# Input_v2_0.net
KiCad netlist of a schematic drawn in EAGLE
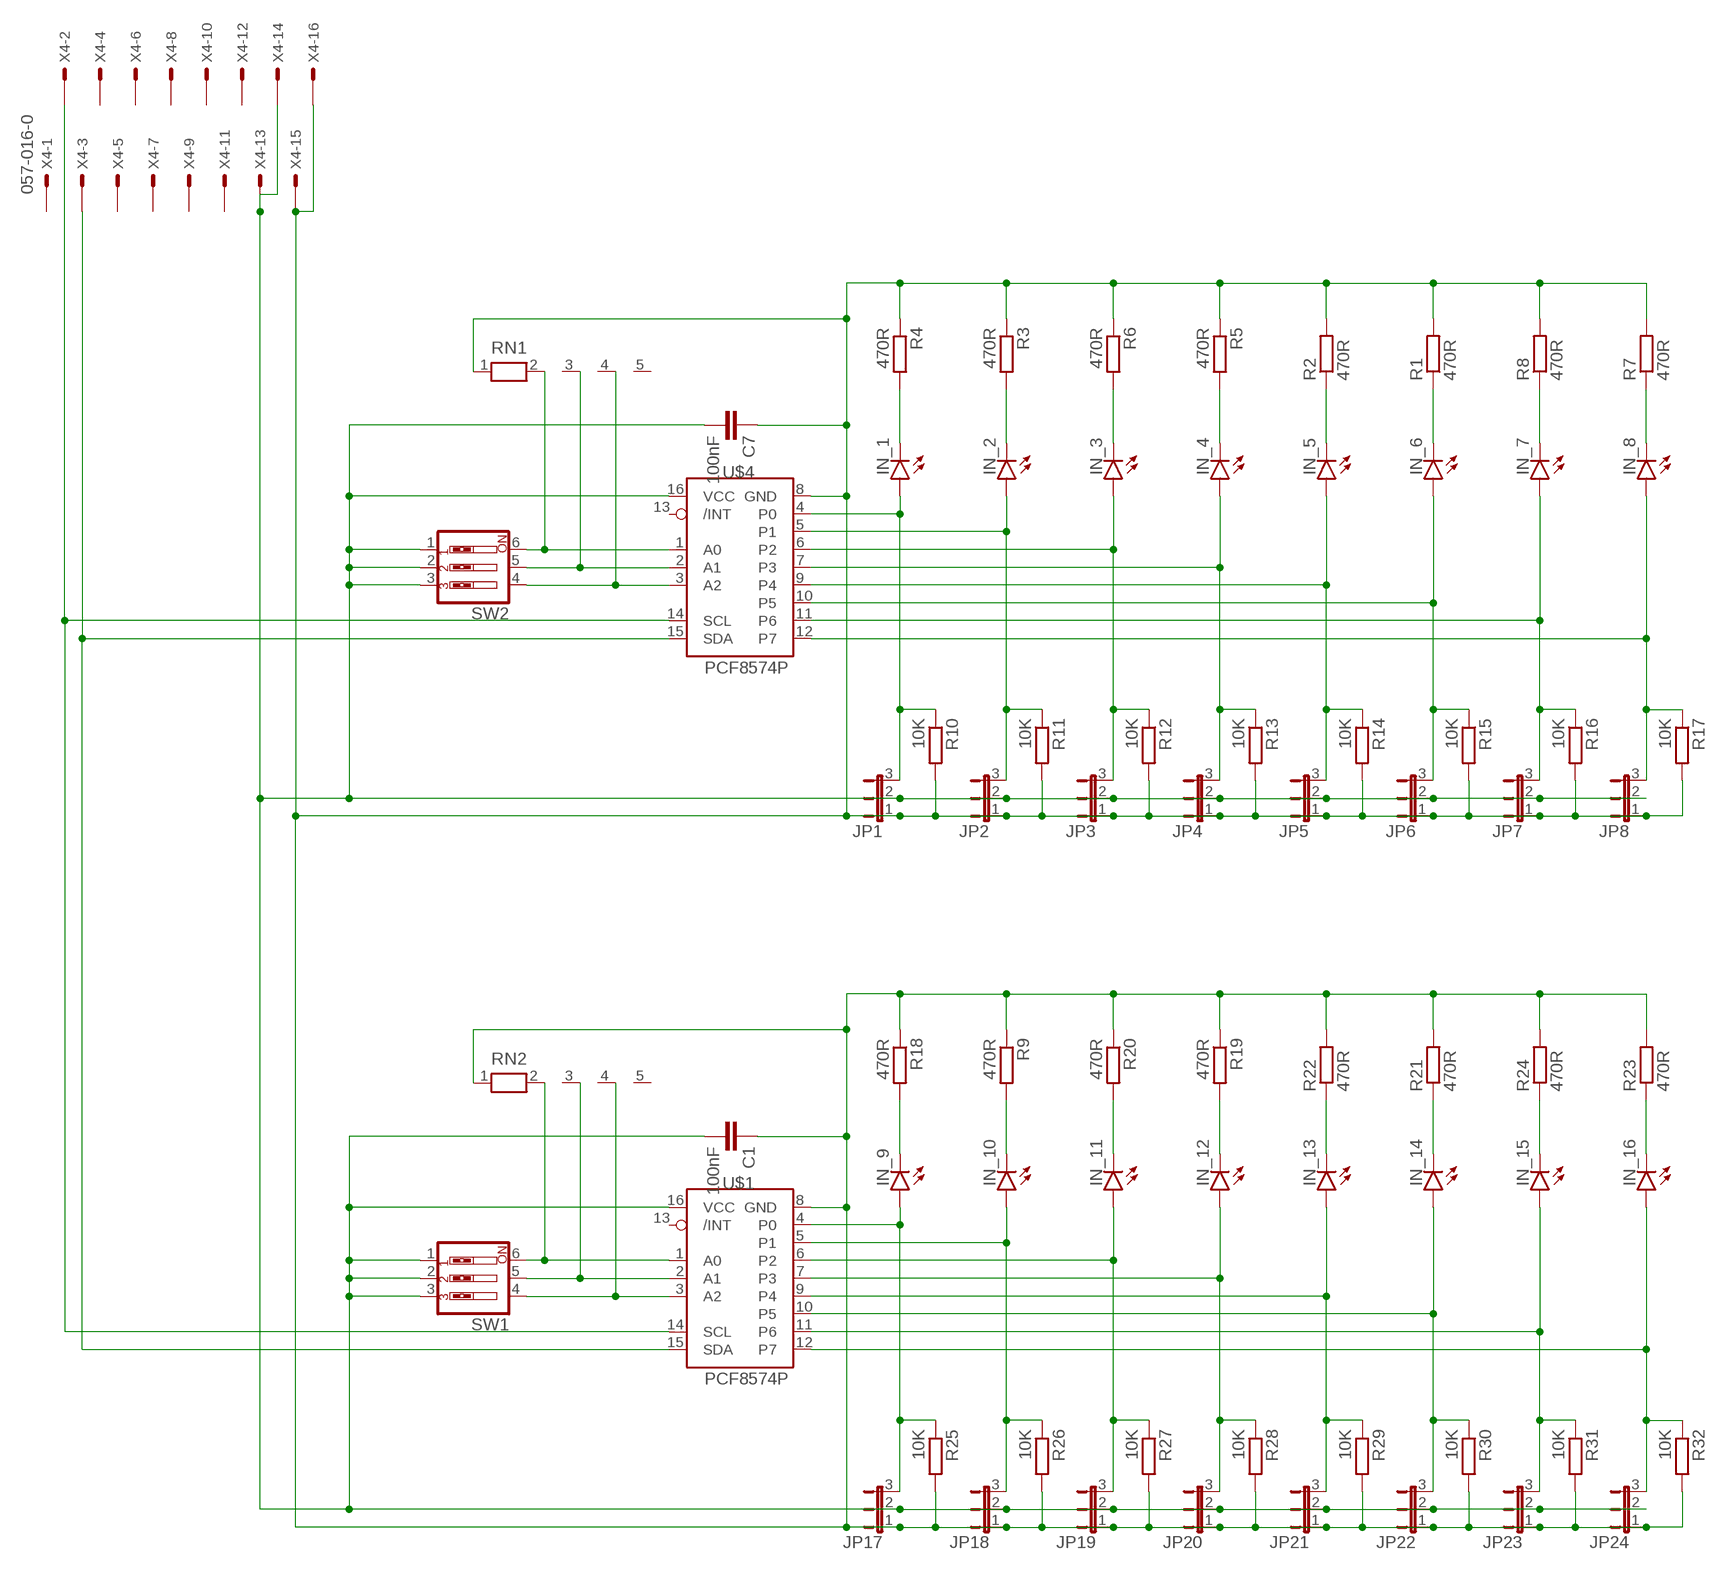
[diagram p0: schematic, sheet 1]

(export (version "E")
  (design (tool "Eeschema 10.0.6"))
  (components
    (comp (ref "C1")
      (value "100nF")
      (footprint "eagle-import:C025-024X044")
      (libsource (lib "eagle-import") (part "C-EU025-024X044"))
    )
    (comp (ref "C7")
      (value "100nF")
      (footprint "eagle-import:C025-024X044")
      (libsource (lib "eagle-import") (part "C-EU025-024X044"))
    )
    (comp (ref "IN_1")
      (value "LED3MM")
      (footprint "eagle-import:LED3MM")
      (libsource (lib "eagle-import") (part "LED3MM"))
    )
    (comp (ref "IN_2")
      (value "LED3MM")
      (footprint "eagle-import:LED3MM")
      (libsource (lib "eagle-import") (part "LED3MM"))
    )
    (comp (ref "IN_3")
      (value "LED3MM")
      (footprint "eagle-import:LED3MM")
      (libsource (lib "eagle-import") (part "LED3MM"))
    )
    (comp (ref "IN_4")
      (value "LED3MM")
      (footprint "eagle-import:LED3MM")
      (libsource (lib "eagle-import") (part "LED3MM"))
    )
    (comp (ref "IN_5")
      (value "LED3MM")
      (footprint "eagle-import:LED3MM")
      (libsource (lib "eagle-import") (part "LED3MM"))
    )
    (comp (ref "IN_6")
      (value "LED3MM")
      (footprint "eagle-import:LED3MM")
      (libsource (lib "eagle-import") (part "LED3MM"))
    )
    (comp (ref "IN_7")
      (value "LED3MM")
      (footprint "eagle-import:LED3MM")
      (libsource (lib "eagle-import") (part "LED3MM"))
    )
    (comp (ref "IN_8")
      (value "LED3MM")
      (footprint "eagle-import:LED3MM")
      (libsource (lib "eagle-import") (part "LED3MM"))
    )
    (comp (ref "IN_9")
      (value "LED3MM")
      (footprint "eagle-import:LED3MM")
      (libsource (lib "eagle-import") (part "LED3MM"))
    )
    (comp (ref "IN_10")
      (value "LED3MM")
      (footprint "eagle-import:LED3MM")
      (libsource (lib "eagle-import") (part "LED3MM"))
    )
    (comp (ref "IN_11")
      (value "LED3MM")
      (footprint "eagle-import:LED3MM")
      (libsource (lib "eagle-import") (part "LED3MM"))
    )
    (comp (ref "IN_12")
      (value "LED3MM")
      (footprint "eagle-import:LED3MM")
      (libsource (lib "eagle-import") (part "LED3MM"))
    )
    (comp (ref "IN_13")
      (value "LED3MM")
      (footprint "eagle-import:LED3MM")
      (libsource (lib "eagle-import") (part "LED3MM"))
    )
    (comp (ref "IN_14")
      (value "LED3MM")
      (footprint "eagle-import:LED3MM")
      (libsource (lib "eagle-import") (part "LED3MM"))
    )
    (comp (ref "IN_15")
      (value "LED3MM")
      (footprint "eagle-import:LED3MM")
      (libsource (lib "eagle-import") (part "LED3MM"))
    )
    (comp (ref "IN_16")
      (value "LED3MM")
      (footprint "eagle-import:LED3MM")
      (libsource (lib "eagle-import") (part "LED3MM"))
    )
    (comp (ref "JP1")
      (value "JP2E")
      (footprint "eagle-import:JP2")
      (libsource (lib "eagle-import") (part "JP2E"))
    )
    (comp (ref "JP2")
      (value "JP2E")
      (footprint "eagle-import:JP2")
      (libsource (lib "eagle-import") (part "JP2E"))
    )
    (comp (ref "JP3")
      (value "JP2E")
      (footprint "eagle-import:JP2")
      (libsource (lib "eagle-import") (part "JP2E"))
    )
    (comp (ref "JP4")
      (value "JP2E")
      (footprint "eagle-import:JP2")
      (libsource (lib "eagle-import") (part "JP2E"))
    )
    (comp (ref "JP5")
      (value "JP2E")
      (footprint "eagle-import:JP2")
      (libsource (lib "eagle-import") (part "JP2E"))
    )
    (comp (ref "JP6")
      (value "JP2E")
      (footprint "eagle-import:JP2")
      (libsource (lib "eagle-import") (part "JP2E"))
    )
    (comp (ref "JP7")
      (value "JP2E")
      (footprint "eagle-import:JP2")
      (libsource (lib "eagle-import") (part "JP2E"))
    )
    (comp (ref "JP8")
      (value "JP2E")
      (footprint "eagle-import:JP2")
      (libsource (lib "eagle-import") (part "JP2E"))
    )
    (comp (ref "JP17")
      (value "JP2E")
      (footprint "eagle-import:JP2")
      (libsource (lib "eagle-import") (part "JP2E"))
    )
    (comp (ref "JP18")
      (value "JP2E")
      (footprint "eagle-import:JP2")
      (libsource (lib "eagle-import") (part "JP2E"))
    )
    (comp (ref "JP19")
      (value "JP2E")
      (footprint "eagle-import:JP2")
      (libsource (lib "eagle-import") (part "JP2E"))
    )
    (comp (ref "JP20")
      (value "JP2E")
      (footprint "eagle-import:JP2")
      (libsource (lib "eagle-import") (part "JP2E"))
    )
    (comp (ref "JP21")
      (value "JP2E")
      (footprint "eagle-import:JP2")
      (libsource (lib "eagle-import") (part "JP2E"))
    )
    (comp (ref "JP22")
      (value "JP2E")
      (footprint "eagle-import:JP2")
      (libsource (lib "eagle-import") (part "JP2E"))
    )
    (comp (ref "JP23")
      (value "JP2E")
      (footprint "eagle-import:JP2")
      (libsource (lib "eagle-import") (part "JP2E"))
    )
    (comp (ref "JP24")
      (value "JP2E")
      (footprint "eagle-import:JP2")
      (libsource (lib "eagle-import") (part "JP2E"))
    )
    (comp (ref "R1")
      (value "470R")
      (footprint "eagle-import:0309_10")
      (libsource (lib "eagle-import") (part "R-EU_0309/10"))
    )
    (comp (ref "R2")
      (value "470R")
      (footprint "eagle-import:0309_10")
      (libsource (lib "eagle-import") (part "R-EU_0309/10"))
    )
    (comp (ref "R3")
      (value "470R")
      (footprint "eagle-import:0309_10")
      (libsource (lib "eagle-import") (part "R-EU_0309/10"))
    )
    (comp (ref "R4")
      (value "470R")
      (footprint "eagle-import:0309_10")
      (libsource (lib "eagle-import") (part "R-EU_0309/10"))
    )
    (comp (ref "R5")
      (value "470R")
      (footprint "eagle-import:0309_10")
      (libsource (lib "eagle-import") (part "R-EU_0309/10"))
    )
    (comp (ref "R6")
      (value "470R")
      (footprint "eagle-import:0309_10")
      (libsource (lib "eagle-import") (part "R-EU_0309/10"))
    )
    (comp (ref "R7")
      (value "470R")
      (footprint "eagle-import:0309_10")
      (libsource (lib "eagle-import") (part "R-EU_0309/10"))
    )
    (comp (ref "R8")
      (value "470R")
      (footprint "eagle-import:0309_10")
      (libsource (lib "eagle-import") (part "R-EU_0309/10"))
    )
    (comp (ref "R9")
      (value "470R")
      (footprint "eagle-import:0309_10")
      (libsource (lib "eagle-import") (part "R-EU_0309/10"))
    )
    (comp (ref "R10")
      (value "10K")
      (footprint "eagle-import:0309_10")
      (libsource (lib "eagle-import") (part "R-EU_0309/10"))
    )
    (comp (ref "R11")
      (value "10K")
      (footprint "eagle-import:0309_10")
      (libsource (lib "eagle-import") (part "R-EU_0309/10"))
    )
    (comp (ref "R12")
      (value "10K")
      (footprint "eagle-import:0309_10")
      (libsource (lib "eagle-import") (part "R-EU_0309/10"))
    )
    (comp (ref "R13")
      (value "10K")
      (footprint "eagle-import:0309_10")
      (libsource (lib "eagle-import") (part "R-EU_0309/10"))
    )
    (comp (ref "R14")
      (value "10K")
      (footprint "eagle-import:0309_10")
      (libsource (lib "eagle-import") (part "R-EU_0309/10"))
    )
    (comp (ref "R15")
      (value "10K")
      (footprint "eagle-import:0309_10")
      (libsource (lib "eagle-import") (part "R-EU_0309/10"))
    )
    (comp (ref "R16")
      (value "10K")
      (footprint "eagle-import:0309_10")
      (libsource (lib "eagle-import") (part "R-EU_0309/10"))
    )
    (comp (ref "R17")
      (value "10K")
      (footprint "eagle-import:0309_10")
      (libsource (lib "eagle-import") (part "R-EU_0309/10"))
    )
    (comp (ref "R18")
      (value "470R")
      (footprint "eagle-import:0309_10")
      (libsource (lib "eagle-import") (part "R-EU_0309/10"))
    )
    (comp (ref "R19")
      (value "470R")
      (footprint "eagle-import:0309_10")
      (libsource (lib "eagle-import") (part "R-EU_0309/10"))
    )
    (comp (ref "R20")
      (value "470R")
      (footprint "eagle-import:0309_10")
      (libsource (lib "eagle-import") (part "R-EU_0309/10"))
    )
    (comp (ref "R21")
      (value "470R")
      (footprint "eagle-import:0309_10")
      (libsource (lib "eagle-import") (part "R-EU_0309/10"))
    )
    (comp (ref "R22")
      (value "470R")
      (footprint "eagle-import:0309_10")
      (libsource (lib "eagle-import") (part "R-EU_0309/10"))
    )
    (comp (ref "R23")
      (value "470R")
      (footprint "eagle-import:0309_10")
      (libsource (lib "eagle-import") (part "R-EU_0309/10"))
    )
    (comp (ref "R24")
      (value "470R")
      (footprint "eagle-import:0309_10")
      (libsource (lib "eagle-import") (part "R-EU_0309/10"))
    )
    (comp (ref "R25")
      (value "10K")
      (footprint "eagle-import:0309_10")
      (libsource (lib "eagle-import") (part "R-EU_0309/10"))
    )
    (comp (ref "R26")
      (value "10K")
      (footprint "eagle-import:0309_10")
      (libsource (lib "eagle-import") (part "R-EU_0309/10"))
    )
    (comp (ref "R27")
      (value "10K")
      (footprint "eagle-import:0309_10")
      (libsource (lib "eagle-import") (part "R-EU_0309/10"))
    )
    (comp (ref "R28")
      (value "10K")
      (footprint "eagle-import:0309_10")
      (libsource (lib "eagle-import") (part "R-EU_0309/10"))
    )
    (comp (ref "R29")
      (value "10K")
      (footprint "eagle-import:0309_10")
      (libsource (lib "eagle-import") (part "R-EU_0309/10"))
    )
    (comp (ref "R30")
      (value "10K")
      (footprint "eagle-import:0309_10")
      (libsource (lib "eagle-import") (part "R-EU_0309/10"))
    )
    (comp (ref "R31")
      (value "10K")
      (footprint "eagle-import:0309_10")
      (libsource (lib "eagle-import") (part "R-EU_0309/10"))
    )
    (comp (ref "R32")
      (value "10K")
      (footprint "eagle-import:0309_10")
      (libsource (lib "eagle-import") (part "R-EU_0309/10"))
    )
    (comp (ref "RN1")
      (value "RN04")
      (footprint "eagle-import:RN-5")
      (libsource (lib "eagle-import") (part "RN04"))
    )
    (comp (ref "RN2")
      (value "RN04")
      (footprint "eagle-import:RN-5")
      (libsource (lib "eagle-import") (part "RN04"))
    )
    (comp (ref "SW1")
      (value "SW_DIP-3")
      (footprint "eagle-import:EDG-03")
      (libsource (lib "eagle-import") (part "SW_DIP-3"))
    )
    (comp (ref "SW2")
      (value "SW_DIP-3")
      (footprint "eagle-import:EDG-03")
      (libsource (lib "eagle-import") (part "SW_DIP-3"))
    )
    (comp (ref "U$1")
      (value "PCF8574P")
      (footprint "eagle-import:DIL16")
      (libsource (lib "eagle-import") (part "PCF8574P"))
    )
    (comp (ref "U$4")
      (value "PCF8574P")
      (footprint "eagle-import:DIL16")
      (libsource (lib "eagle-import") (part "PCF8574P"))
    )
    (comp (ref "X4")
      (value "057-016-0")
      (footprint "eagle-import:057-016-0")
      (libsource (lib "eagle-import") (part "057-016-0"))
    )
  )
  (nets
    (net (code "1") (name "Net-(IN_1-C)") (class "Default")
      (node (ref "IN_1") (pin "K") (pinfunction "C_K") (pintype "passive"))
      (node (ref "R4") (pin "2") (pinfunction "2_2") (pintype "passive"))
    )
    (net (code "2") (name "Net-(IN_2-C)") (class "Default")
      (node (ref "IN_2") (pin "K") (pinfunction "C_K") (pintype "passive"))
      (node (ref "R3") (pin "2") (pinfunction "2_2") (pintype "passive"))
    )
    (net (code "3") (name "Net-(IN_3-C)") (class "Default")
      (node (ref "IN_3") (pin "K") (pinfunction "C_K") (pintype "passive"))
      (node (ref "R6") (pin "2") (pinfunction "2_2") (pintype "passive"))
    )
    (net (code "4") (name "Net-(IN_4-C)") (class "Default")
      (node (ref "IN_4") (pin "K") (pinfunction "C_K") (pintype "passive"))
      (node (ref "R5") (pin "2") (pinfunction "2_2") (pintype "passive"))
    )
    (net (code "5") (name "Net-(IN_5-C)") (class "Default")
      (node (ref "IN_5") (pin "K") (pinfunction "C_K") (pintype "passive"))
      (node (ref "R2") (pin "1") (pinfunction "1_1") (pintype "passive"))
    )
    (net (code "6") (name "Net-(IN_6-C)") (class "Default")
      (node (ref "IN_6") (pin "K") (pinfunction "C_K") (pintype "passive"))
      (node (ref "R1") (pin "1") (pinfunction "1_1") (pintype "passive"))
    )
    (net (code "7") (name "Net-(IN_7-C)") (class "Default")
      (node (ref "IN_7") (pin "K") (pinfunction "C_K") (pintype "passive"))
      (node (ref "R8") (pin "1") (pinfunction "1_1") (pintype "passive"))
    )
    (net (code "8") (name "Net-(IN_8-C)") (class "Default")
      (node (ref "IN_8") (pin "K") (pinfunction "C_K") (pintype "passive"))
      (node (ref "R7") (pin "1") (pinfunction "1_1") (pintype "passive"))
    )
    (net (code "9") (name "Net-(IN_9-C)") (class "Default")
      (node (ref "IN_9") (pin "K") (pinfunction "C_K") (pintype "passive"))
      (node (ref "R18") (pin "2") (pinfunction "2_2") (pintype "passive"))
    )
    (net (code "10") (name "Net-(IN_10-C)") (class "Default")
      (node (ref "IN_10") (pin "K") (pinfunction "C_K") (pintype "passive"))
      (node (ref "R9") (pin "2") (pinfunction "2_2") (pintype "passive"))
    )
    (net (code "11") (name "Net-(IN_11-C)") (class "Default")
      (node (ref "IN_11") (pin "K") (pinfunction "C_K") (pintype "passive"))
      (node (ref "R20") (pin "2") (pinfunction "2_2") (pintype "passive"))
    )
    (net (code "12") (name "Net-(IN_12-C)") (class "Default")
      (node (ref "IN_12") (pin "K") (pinfunction "C_K") (pintype "passive"))
      (node (ref "R19") (pin "2") (pinfunction "2_2") (pintype "passive"))
    )
    (net (code "13") (name "Net-(IN_13-C)") (class "Default")
      (node (ref "IN_13") (pin "K") (pinfunction "C_K") (pintype "passive"))
      (node (ref "R22") (pin "1") (pinfunction "1_1") (pintype "passive"))
    )
    (net (code "14") (name "Net-(IN_14-C)") (class "Default")
      (node (ref "IN_14") (pin "K") (pinfunction "C_K") (pintype "passive"))
      (node (ref "R21") (pin "1") (pinfunction "1_1") (pintype "passive"))
    )
    (net (code "15") (name "Net-(IN_15-C)") (class "Default")
      (node (ref "IN_15") (pin "K") (pinfunction "C_K") (pintype "passive"))
      (node (ref "R24") (pin "1") (pinfunction "1_1") (pintype "passive"))
    )
    (net (code "16") (name "Net-(IN_16-C)") (class "Default")
      (node (ref "IN_16") (pin "K") (pinfunction "C_K") (pintype "passive"))
      (node (ref "R23") (pin "1") (pinfunction "1_1") (pintype "passive"))
    )
    (net (code "17") (name "Net-(U$1-A0)") (class "Default")
      (node (ref "RN2") (pin "2") (pinfunction "2_2") (pintype "passive"))
      (node (ref "SW1") (pin "6") (pinfunction "6_6") (pintype "passive"))
      (node (ref "U$1") (pin "1") (pinfunction "A0_1") (pintype "input"))
    )
    (net (code "18") (name "Net-(U$1-A1)") (class "Default")
      (node (ref "RN2") (pin "3") (pinfunction "3_3") (pintype "passive"))
      (node (ref "SW1") (pin "5") (pinfunction "5_5") (pintype "passive"))
      (node (ref "U$1") (pin "2") (pinfunction "A1_2") (pintype "input"))
    )
    (net (code "19") (name "Net-(U$1-A2)") (class "Default")
      (node (ref "RN2") (pin "4") (pinfunction "4_4") (pintype "passive"))
      (node (ref "SW1") (pin "4") (pinfunction "4_4") (pintype "passive"))
      (node (ref "U$1") (pin "3") (pinfunction "A2_3") (pintype "input"))
    )
    (net (code "20") (name "Net-(U$1-GND)") (class "Default")
      (node (ref "C1") (pin "1") (pinfunction "1_1") (pintype "passive"))
      (node (ref "C7") (pin "1") (pinfunction "1_1") (pintype "passive"))
      (node (ref "JP1") (pin "1") (pinfunction "1_1") (pintype "passive"))
      (node (ref "JP17") (pin "1") (pinfunction "1_1") (pintype "passive"))
      (node (ref "JP18") (pin "1") (pinfunction "1_1") (pintype "passive"))
      (node (ref "JP19") (pin "1") (pinfunction "1_1") (pintype "passive"))
      (node (ref "JP2") (pin "1") (pinfunction "1_1") (pintype "passive"))
      (node (ref "JP20") (pin "1") (pinfunction "1_1") (pintype "passive"))
      (node (ref "JP21") (pin "1") (pinfunction "1_1") (pintype "passive"))
      (node (ref "JP22") (pin "1") (pinfunction "1_1") (pintype "passive"))
      (node (ref "JP23") (pin "1") (pinfunction "1_1") (pintype "passive"))
      (node (ref "JP24") (pin "1") (pinfunction "1_1") (pintype "passive"))
      (node (ref "JP3") (pin "1") (pinfunction "1_1") (pintype "passive"))
      (node (ref "JP4") (pin "1") (pinfunction "1_1") (pintype "passive"))
      (node (ref "JP5") (pin "1") (pinfunction "1_1") (pintype "passive"))
      (node (ref "JP6") (pin "1") (pinfunction "1_1") (pintype "passive"))
      (node (ref "JP7") (pin "1") (pinfunction "1_1") (pintype "passive"))
      (node (ref "JP8") (pin "1") (pinfunction "1_1") (pintype "passive"))
      (node (ref "R1") (pin "2") (pinfunction "2_2") (pintype "passive"))
      (node (ref "R10") (pin "2") (pinfunction "2_2") (pintype "passive"))
      (node (ref "R11") (pin "2") (pinfunction "2_2") (pintype "passive"))
      (node (ref "R12") (pin "2") (pinfunction "2_2") (pintype "passive"))
      (node (ref "R13") (pin "2") (pinfunction "2_2") (pintype "passive"))
      (node (ref "R14") (pin "2") (pinfunction "2_2") (pintype "passive"))
      (node (ref "R15") (pin "2") (pinfunction "2_2") (pintype "passive"))
      (node (ref "R16") (pin "2") (pinfunction "2_2") (pintype "passive"))
      (node (ref "R17") (pin "2") (pinfunction "2_2") (pintype "passive"))
      (node (ref "R18") (pin "1") (pinfunction "1_1") (pintype "passive"))
      (node (ref "R19") (pin "1") (pinfunction "1_1") (pintype "passive"))
      (node (ref "R2") (pin "2") (pinfunction "2_2") (pintype "passive"))
      (node (ref "R20") (pin "1") (pinfunction "1_1") (pintype "passive"))
      (node (ref "R21") (pin "2") (pinfunction "2_2") (pintype "passive"))
      (node (ref "R22") (pin "2") (pinfunction "2_2") (pintype "passive"))
      (node (ref "R23") (pin "2") (pinfunction "2_2") (pintype "passive"))
      (node (ref "R24") (pin "2") (pinfunction "2_2") (pintype "passive"))
      (node (ref "R25") (pin "2") (pinfunction "2_2") (pintype "passive"))
      (node (ref "R26") (pin "2") (pinfunction "2_2") (pintype "passive"))
      (node (ref "R27") (pin "2") (pinfunction "2_2") (pintype "passive"))
      (node (ref "R28") (pin "2") (pinfunction "2_2") (pintype "passive"))
      (node (ref "R29") (pin "2") (pinfunction "2_2") (pintype "passive"))
      (node (ref "R3") (pin "1") (pinfunction "1_1") (pintype "passive"))
      (node (ref "R30") (pin "2") (pinfunction "2_2") (pintype "passive"))
      (node (ref "R31") (pin "2") (pinfunction "2_2") (pintype "passive"))
      (node (ref "R32") (pin "2") (pinfunction "2_2") (pintype "passive"))
      (node (ref "R4") (pin "1") (pinfunction "1_1") (pintype "passive"))
      (node (ref "R5") (pin "1") (pinfunction "1_1") (pintype "passive"))
      (node (ref "R6") (pin "1") (pinfunction "1_1") (pintype "passive"))
      (node (ref "R7") (pin "2") (pinfunction "2_2") (pintype "passive"))
      (node (ref "R8") (pin "2") (pinfunction "2_2") (pintype "passive"))
      (node (ref "R9") (pin "1") (pinfunction "1_1") (pintype "passive"))
      (node (ref "RN1") (pin "1") (pinfunction "1_1") (pintype "passive"))
      (node (ref "RN2") (pin "1") (pinfunction "1_1") (pintype "passive"))
      (node (ref "U$1") (pin "8") (pinfunction "GND_8") (pintype "power_in"))
      (node (ref "U$4") (pin "8") (pinfunction "GND_8") (pintype "power_in"))
      (node (ref "X4") (pin "15") (pinfunction "S_15") (pintype "passive"))
      (node (ref "X4") (pin "16") (pinfunction "S_16") (pintype "passive"))
    )
    (net (code "21") (name "Net-(U$1-P0)") (class "Default")
      (node (ref "IN_9") (pin "A") (pinfunction "A_A") (pintype "passive"))
      (node (ref "JP17") (pin "3") (pinfunction "3_3") (pintype "passive"))
      (node (ref "R25") (pin "1") (pinfunction "1_1") (pintype "passive"))
      (node (ref "U$1") (pin "4") (pinfunction "P0_4") (pintype "bidirectional"))
    )
    (net (code "22") (name "Net-(U$1-P1)") (class "Default")
      (node (ref "IN_10") (pin "A") (pinfunction "A_A") (pintype "passive"))
      (node (ref "JP18") (pin "3") (pinfunction "3_3") (pintype "passive"))
      (node (ref "R26") (pin "1") (pinfunction "1_1") (pintype "passive"))
      (node (ref "U$1") (pin "5") (pinfunction "P1_5") (pintype "bidirectional"))
    )
    (net (code "23") (name "Net-(U$1-P2)") (class "Default")
      (node (ref "IN_11") (pin "A") (pinfunction "A_A") (pintype "passive"))
      (node (ref "JP19") (pin "3") (pinfunction "3_3") (pintype "passive"))
      (node (ref "R27") (pin "1") (pinfunction "1_1") (pintype "passive"))
      (node (ref "U$1") (pin "6") (pinfunction "P2_6") (pintype "bidirectional"))
    )
    (net (code "24") (name "Net-(U$1-P3)") (class "Default")
      (node (ref "IN_12") (pin "A") (pinfunction "A_A") (pintype "passive"))
      (node (ref "JP20") (pin "3") (pinfunction "3_3") (pintype "passive"))
      (node (ref "R28") (pin "1") (pinfunction "1_1") (pintype "passive"))
      (node (ref "U$1") (pin "7") (pinfunction "P3_7") (pintype "bidirectional"))
    )
    (net (code "25") (name "Net-(U$1-P4)") (class "Default")
      (node (ref "IN_13") (pin "A") (pinfunction "A_A") (pintype "passive"))
      (node (ref "JP21") (pin "3") (pinfunction "3_3") (pintype "passive"))
      (node (ref "R29") (pin "1") (pinfunction "1_1") (pintype "passive"))
      (node (ref "U$1") (pin "9") (pinfunction "P4_9") (pintype "bidirectional"))
    )
    (net (code "26") (name "Net-(U$1-P5)") (class "Default")
      (node (ref "IN_14") (pin "A") (pinfunction "A_A") (pintype "passive"))
      (node (ref "JP22") (pin "3") (pinfunction "3_3") (pintype "passive"))
      (node (ref "R30") (pin "1") (pinfunction "1_1") (pintype "passive"))
      (node (ref "U$1") (pin "10") (pinfunction "P5_10") (pintype "bidirectional"))
    )
    (net (code "27") (name "Net-(U$1-P6)") (class "Default")
      (node (ref "IN_15") (pin "A") (pinfunction "A_A") (pintype "passive"))
      (node (ref "JP23") (pin "3") (pinfunction "3_3") (pintype "passive"))
      (node (ref "R31") (pin "1") (pinfunction "1_1") (pintype "passive"))
      (node (ref "U$1") (pin "11") (pinfunction "P6_11") (pintype "bidirectional"))
    )
    (net (code "28") (name "Net-(U$1-P7)") (class "Default")
      (node (ref "IN_16") (pin "A") (pinfunction "A_A") (pintype "passive"))
      (node (ref "JP24") (pin "3") (pinfunction "3_3") (pintype "passive"))
      (node (ref "R32") (pin "1") (pinfunction "1_1") (pintype "passive"))
      (node (ref "U$1") (pin "12") (pinfunction "P7_12") (pintype "bidirectional"))
    )
    (net (code "29") (name "Net-(U$1-SCL)") (class "Default")
      (node (ref "U$1") (pin "14") (pinfunction "SCL_14") (pintype "input"))
      (node (ref "U$4") (pin "14") (pinfunction "SCL_14") (pintype "input"))
      (node (ref "X4") (pin "2") (pinfunction "S_2") (pintype "passive"))
    )
    (net (code "30") (name "Net-(U$1-SDA)") (class "Default")
      (node (ref "U$1") (pin "15") (pinfunction "SDA_15") (pintype "bidirectional"))
      (node (ref "U$4") (pin "15") (pinfunction "SDA_15") (pintype "bidirectional"))
      (node (ref "X4") (pin "3") (pinfunction "S_3") (pintype "passive"))
    )
    (net (code "31") (name "Net-(U$1-VCC)") (class "Default")
      (node (ref "C1") (pin "2") (pinfunction "2_2") (pintype "passive"))
      (node (ref "C7") (pin "2") (pinfunction "2_2") (pintype "passive"))
      (node (ref "JP1") (pin "2") (pinfunction "2_2") (pintype "passive"))
      (node (ref "JP17") (pin "2") (pinfunction "2_2") (pintype "passive"))
      (node (ref "JP18") (pin "2") (pinfunction "2_2") (pintype "passive"))
      (node (ref "JP19") (pin "2") (pinfunction "2_2") (pintype "passive"))
      (node (ref "JP2") (pin "2") (pinfunction "2_2") (pintype "passive"))
      (node (ref "JP20") (pin "2") (pinfunction "2_2") (pintype "passive"))
      (node (ref "JP21") (pin "2") (pinfunction "2_2") (pintype "passive"))
      (node (ref "JP22") (pin "2") (pinfunction "2_2") (pintype "passive"))
      (node (ref "JP23") (pin "2") (pinfunction "2_2") (pintype "passive"))
      (node (ref "JP24") (pin "2") (pinfunction "2_2") (pintype "passive"))
      (node (ref "JP3") (pin "2") (pinfunction "2_2") (pintype "passive"))
      (node (ref "JP4") (pin "2") (pinfunction "2_2") (pintype "passive"))
      (node (ref "JP5") (pin "2") (pinfunction "2_2") (pintype "passive"))
      (node (ref "JP6") (pin "2") (pinfunction "2_2") (pintype "passive"))
      (node (ref "JP7") (pin "2") (pinfunction "2_2") (pintype "passive"))
      (node (ref "JP8") (pin "2") (pinfunction "2_2") (pintype "passive"))
      (node (ref "SW1") (pin "1") (pinfunction "1_1") (pintype "passive"))
      (node (ref "SW1") (pin "2") (pinfunction "2_2") (pintype "passive"))
      (node (ref "SW1") (pin "3") (pinfunction "3_3") (pintype "passive"))
      (node (ref "SW2") (pin "1") (pinfunction "1_1") (pintype "passive"))
      (node (ref "SW2") (pin "2") (pinfunction "2_2") (pintype "passive"))
      (node (ref "SW2") (pin "3") (pinfunction "3_3") (pintype "passive"))
      (node (ref "U$1") (pin "16") (pinfunction "VCC_16") (pintype "power_in"))
      (node (ref "U$4") (pin "16") (pinfunction "VCC_16") (pintype "power_in"))
      (node (ref "X4") (pin "13") (pinfunction "S_13") (pintype "passive"))
      (node (ref "X4") (pin "14") (pinfunction "S_14") (pintype "passive"))
    )
    (net (code "32") (name "Net-(U$4-A0)") (class "Default")
      (node (ref "RN1") (pin "2") (pinfunction "2_2") (pintype "passive"))
      (node (ref "SW2") (pin "6") (pinfunction "6_6") (pintype "passive"))
      (node (ref "U$4") (pin "1") (pinfunction "A0_1") (pintype "input"))
    )
    (net (code "33") (name "Net-(U$4-A1)") (class "Default")
      (node (ref "RN1") (pin "3") (pinfunction "3_3") (pintype "passive"))
      (node (ref "SW2") (pin "5") (pinfunction "5_5") (pintype "passive"))
      (node (ref "U$4") (pin "2") (pinfunction "A1_2") (pintype "input"))
    )
    (net (code "34") (name "Net-(U$4-A2)") (class "Default")
      (node (ref "RN1") (pin "4") (pinfunction "4_4") (pintype "passive"))
      (node (ref "SW2") (pin "4") (pinfunction "4_4") (pintype "passive"))
      (node (ref "U$4") (pin "3") (pinfunction "A2_3") (pintype "input"))
    )
    (net (code "35") (name "Net-(U$4-P0)") (class "Default")
      (node (ref "IN_1") (pin "A") (pinfunction "A_A") (pintype "passive"))
      (node (ref "JP1") (pin "3") (pinfunction "3_3") (pintype "passive"))
      (node (ref "R10") (pin "1") (pinfunction "1_1") (pintype "passive"))
      (node (ref "U$4") (pin "4") (pinfunction "P0_4") (pintype "bidirectional"))
    )
    (net (code "36") (name "Net-(U$4-P1)") (class "Default")
      (node (ref "IN_2") (pin "A") (pinfunction "A_A") (pintype "passive"))
      (node (ref "JP2") (pin "3") (pinfunction "3_3") (pintype "passive"))
      (node (ref "R11") (pin "1") (pinfunction "1_1") (pintype "passive"))
      (node (ref "U$4") (pin "5") (pinfunction "P1_5") (pintype "bidirectional"))
    )
    (net (code "37") (name "Net-(U$4-P2)") (class "Default")
      (node (ref "IN_3") (pin "A") (pinfunction "A_A") (pintype "passive"))
      (node (ref "JP3") (pin "3") (pinfunction "3_3") (pintype "passive"))
      (node (ref "R12") (pin "1") (pinfunction "1_1") (pintype "passive"))
      (node (ref "U$4") (pin "6") (pinfunction "P2_6") (pintype "bidirectional"))
    )
    (net (code "38") (name "Net-(U$4-P3)") (class "Default")
      (node (ref "IN_4") (pin "A") (pinfunction "A_A") (pintype "passive"))
      (node (ref "JP4") (pin "3") (pinfunction "3_3") (pintype "passive"))
      (node (ref "R13") (pin "1") (pinfunction "1_1") (pintype "passive"))
      (node (ref "U$4") (pin "7") (pinfunction "P3_7") (pintype "bidirectional"))
    )
    (net (code "39") (name "Net-(U$4-P4)") (class "Default")
      (node (ref "IN_5") (pin "A") (pinfunction "A_A") (pintype "passive"))
      (node (ref "JP5") (pin "3") (pinfunction "3_3") (pintype "passive"))
      (node (ref "R14") (pin "1") (pinfunction "1_1") (pintype "passive"))
      (node (ref "U$4") (pin "9") (pinfunction "P4_9") (pintype "bidirectional"))
    )
    (net (code "40") (name "Net-(U$4-P5)") (class "Default")
      (node (ref "IN_6") (pin "A") (pinfunction "A_A") (pintype "passive"))
      (node (ref "JP6") (pin "3") (pinfunction "3_3") (pintype "passive"))
      (node (ref "R15") (pin "1") (pinfunction "1_1") (pintype "passive"))
      (node (ref "U$4") (pin "10") (pinfunction "P5_10") (pintype "bidirectional"))
    )
    (net (code "41") (name "Net-(U$4-P6)") (class "Default")
      (node (ref "IN_7") (pin "A") (pinfunction "A_A") (pintype "passive"))
      (node (ref "JP7") (pin "3") (pinfunction "3_3") (pintype "passive"))
      (node (ref "R16") (pin "1") (pinfunction "1_1") (pintype "passive"))
      (node (ref "U$4") (pin "11") (pinfunction "P6_11") (pintype "bidirectional"))
    )
    (net (code "42") (name "Net-(U$4-P7)") (class "Default")
      (node (ref "IN_8") (pin "A") (pinfunction "A_A") (pintype "passive"))
      (node (ref "JP8") (pin "3") (pinfunction "3_3") (pintype "passive"))
      (node (ref "R17") (pin "1") (pinfunction "1_1") (pintype "passive"))
      (node (ref "U$4") (pin "12") (pinfunction "P7_12") (pintype "bidirectional"))
    )
    (net (code "43") (name "unconnected-(RN1-Pad5)") (class "Default")
      (node (ref "RN1") (pin "5") (pinfunction "5_5") (pintype "passive"))
    )
    (net (code "44") (name "unconnected-(RN2-Pad5)") (class "Default")
      (node (ref "RN2") (pin "5") (pinfunction "5_5") (pintype "passive"))
    )
    (net (code "45") (name "unconnected-(U$1-{slash}INT-Pad13)") (class "Default")
      (node (ref "U$1") (pin "13") (pinfunction "/INT_13") (pintype "output"))
    )
    (net (code "46") (name "unconnected-(U$4-{slash}INT-Pad13)") (class "Default")
      (node (ref "U$4") (pin "13") (pinfunction "/INT_13") (pintype "output"))
    )
    (net (code "47") (name "unconnected-(X4A-S-Pad1)") (class "Default")
      (node (ref "X4") (pin "1") (pinfunction "S_1") (pintype "passive"))
    )
    (net (code "48") (name "unconnected-(X4B-S-Pad10)") (class "Default")
      (node (ref "X4") (pin "10") (pinfunction "S_10") (pintype "passive"))
    )
    (net (code "49") (name "unconnected-(X4C-S-Pad11)") (class "Default")
      (node (ref "X4") (pin "11") (pinfunction "S_11") (pintype "passive"))
    )
    (net (code "50") (name "unconnected-(X4D-S-Pad12)") (class "Default")
      (node (ref "X4") (pin "12") (pinfunction "S_12") (pintype "passive"))
    )
    (net (code "51") (name "unconnected-(X4K-S-Pad4)") (class "Default")
      (node (ref "X4") (pin "4") (pinfunction "S_4") (pintype "passive"))
    )
    (net (code "52") (name "unconnected-(X4L-S-Pad5)") (class "Default")
      (node (ref "X4") (pin "5") (pinfunction "S_5") (pintype "passive"))
    )
    (net (code "53") (name "unconnected-(X4M-S-Pad6)") (class "Default")
      (node (ref "X4") (pin "6") (pinfunction "S_6") (pintype "passive"))
    )
    (net (code "54") (name "unconnected-(X4N-S-Pad7)") (class "Default")
      (node (ref "X4") (pin "7") (pinfunction "S_7") (pintype "passive"))
    )
    (net (code "55") (name "unconnected-(X4O-S-Pad8)") (class "Default")
      (node (ref "X4") (pin "8") (pinfunction "S_8") (pintype "passive"))
    )
    (net (code "56") (name "unconnected-(X4P-S-Pad9)") (class "Default")
      (node (ref "X4") (pin "9") (pinfunction "S_9") (pintype "passive"))
    )
  )
)
